# combo-03_1.net
KiCad netlist of a schematic drawn in EAGLE
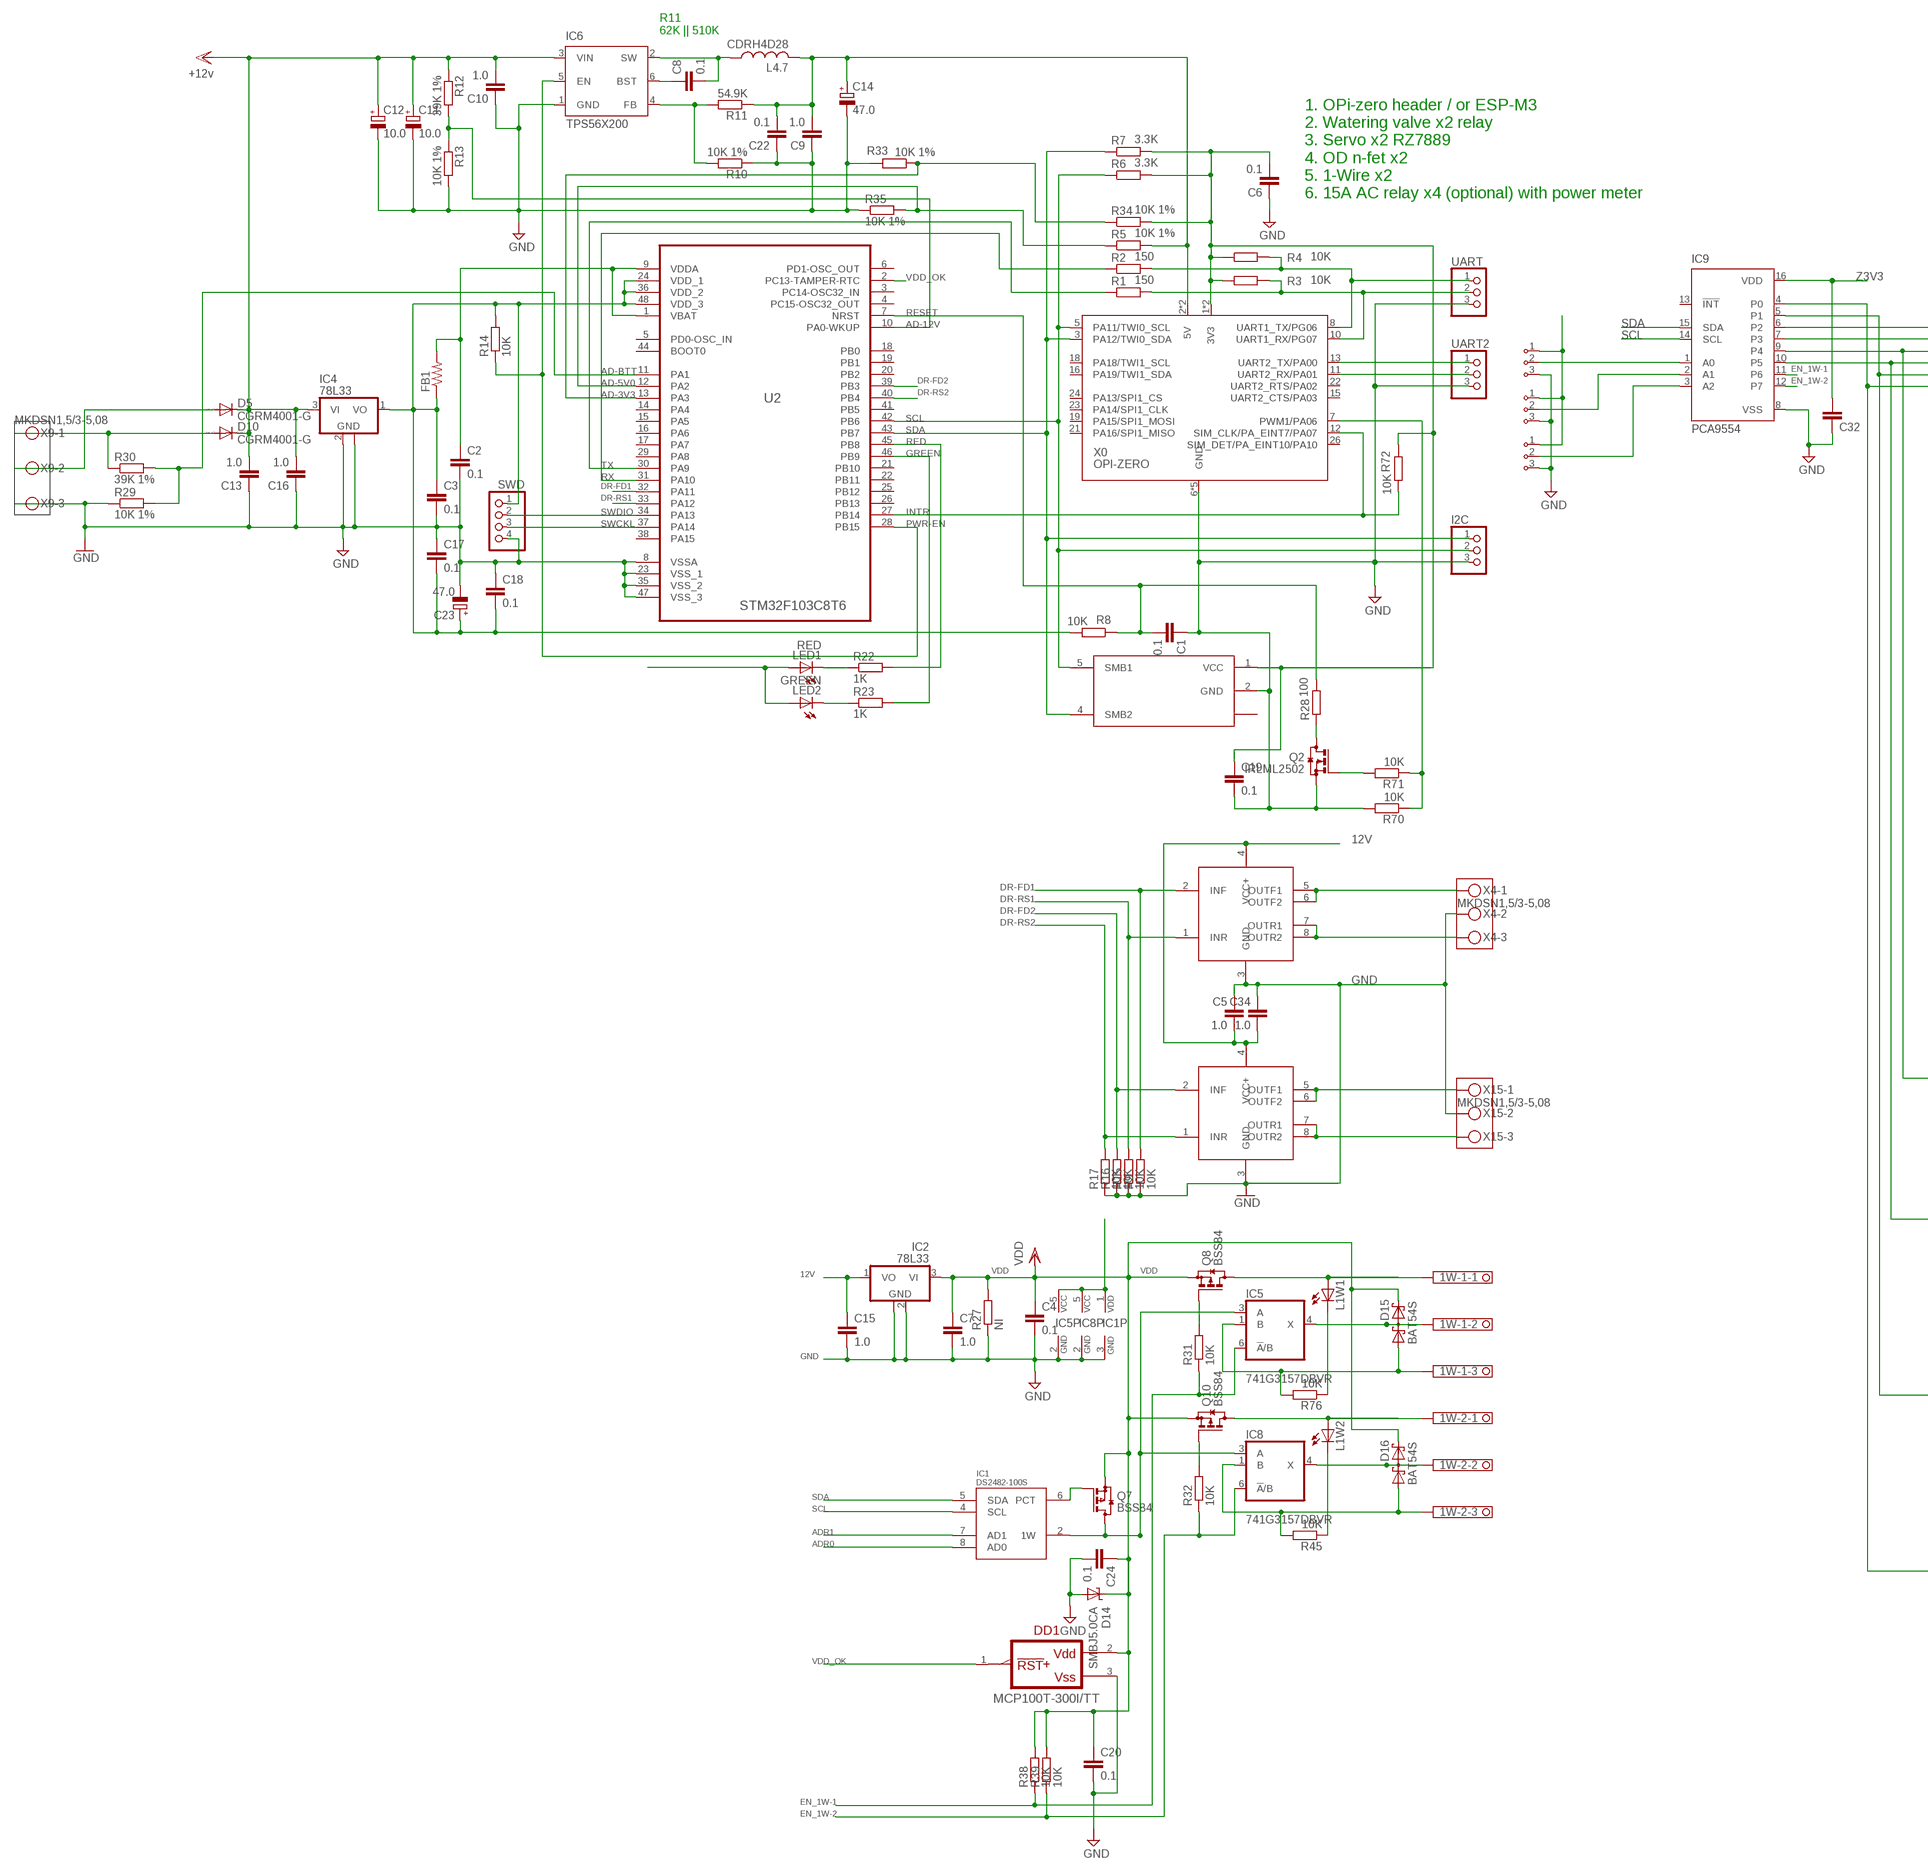
[diagram p0: schematic, sheet 1, part 1 of 2]
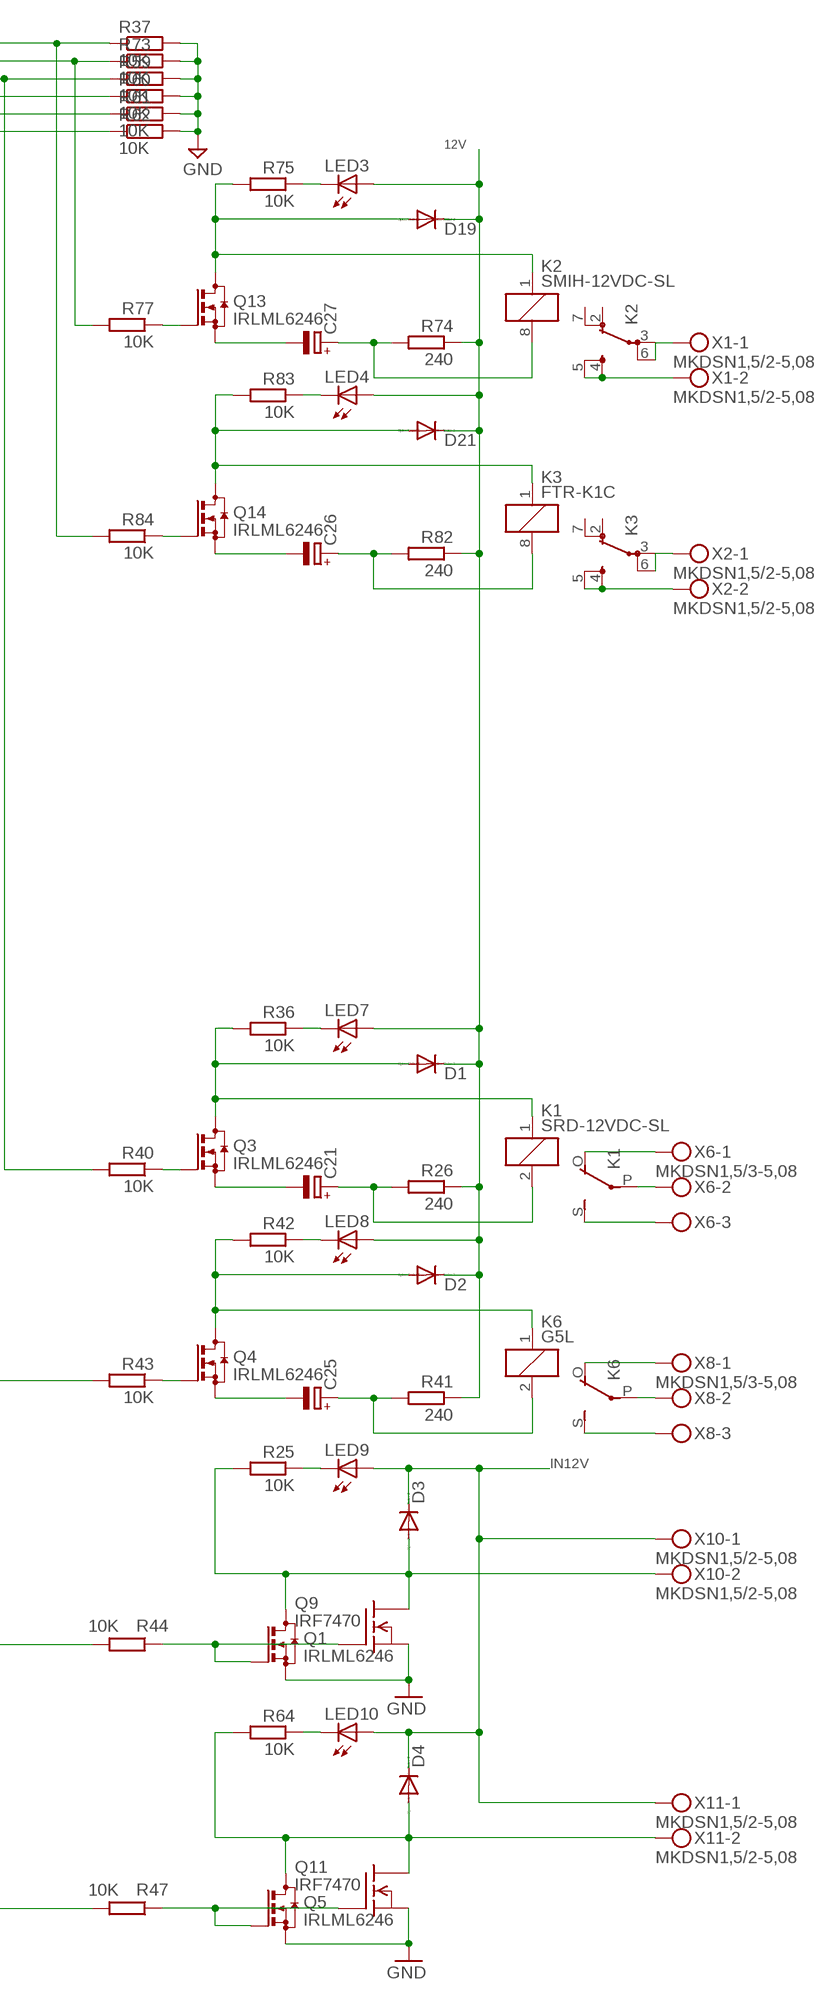
[diagram p1: schematic, sheet 1, part 2 of 2]

(export (version "E")
  (design (tool "Eeschema 10.0.6"))
  (components
    (comp (ref "1W-1")
      (value "1751251")
      (footprint "eagle-import:1751251")
      (libsource (lib "eagle-import") (part "1751251"))
    )
    (comp (ref "1W-2")
      (value "1751251")
      (footprint "eagle-import:1751251")
      (libsource (lib "eagle-import") (part "1751251"))
    )
    (comp (ref "A0")
      (value "ADDR3PIN0603")
      (footprint "eagle-import:0603-3PIN")
      (libsource (lib "eagle-import") (part "ADDR3PIN0603"))
    )
    (comp (ref "A1")
      (value "ADDR3PIN0603")
      (footprint "eagle-import:0603-3PIN")
      (libsource (lib "eagle-import") (part "ADDR3PIN0603"))
    )
    (comp (ref "A2")
      (value "ADDR3PIN0603")
      (footprint "eagle-import:0603-3PIN")
      (libsource (lib "eagle-import") (part "ADDR3PIN0603"))
    )
    (comp (ref "C1")
      (value "0.1")
      (footprint "eagle-import:C0603")
      (libsource (lib "eagle-import") (part "C-EUC0603"))
    )
    (comp (ref "C2")
      (value "0.1")
      (footprint "eagle-import:C0603")
      (libsource (lib "eagle-import") (part "C-EUC0603"))
    )
    (comp (ref "C3")
      (value "0.1")
      (footprint "eagle-import:C0603")
      (libsource (lib "eagle-import") (part "C-EUC0603"))
    )
    (comp (ref "C4")
      (value "0.1")
      (footprint "eagle-import:C0603")
      (libsource (lib "eagle-import") (part "C-EUC0603"))
    )
    (comp (ref "C5")
      (value "1.0")
      (footprint "eagle-import:C0805")
      (libsource (lib "eagle-import") (part "C-EUC0805"))
    )
    (comp (ref "C6")
      (value "0.1")
      (footprint "eagle-import:C0805")
      (libsource (lib "eagle-import") (part "C-EUC0805"))
    )
    (comp (ref "C7")
      (value "1.0")
      (footprint "eagle-import:C0805")
      (libsource (lib "eagle-import") (part "C-EUC0805"))
    )
    (comp (ref "C8")
      (value "0.1")
      (footprint "eagle-import:C0805")
      (libsource (lib "eagle-import") (part "C-EUC0805"))
    )
    (comp (ref "C9")
      (value "1.0")
      (footprint "eagle-import:C0805")
      (libsource (lib "eagle-import") (part "C-EUC0805"))
    )
    (comp (ref "C10")
      (value "1.0")
      (footprint "eagle-import:C1206")
      (libsource (lib "eagle-import") (part "C-EUC1206"))
    )
    (comp (ref "C11")
      (value "10.0")
      (footprint "eagle-import:C_6032-28R")
      (libsource (lib "eagle-import") (part "CPOL-EUC/6032-28R"))
    )
    (comp (ref "C12")
      (value "10.0")
      (footprint "eagle-import:C_6032-28R")
      (libsource (lib "eagle-import") (part "CPOL-EUC/6032-28R"))
    )
    (comp (ref "C13")
      (value "1.0")
      (footprint "eagle-import:C1206")
      (libsource (lib "eagle-import") (part "C-EUC1206"))
    )
    (comp (ref "C14")
      (value "47.0")
      (footprint "eagle-import:B_3528-21R")
      (libsource (lib "eagle-import") (part "CPOL-EUB/3528-21R"))
    )
    (comp (ref "C15")
      (value "1.0")
      (footprint "eagle-import:C0805")
      (libsource (lib "eagle-import") (part "C-EUC0805"))
    )
    (comp (ref "C16")
      (value "1.0")
      (footprint "eagle-import:C1206")
      (libsource (lib "eagle-import") (part "C-EUC1206"))
    )
    (comp (ref "C17")
      (value "0.1")
      (footprint "eagle-import:C0603")
      (libsource (lib "eagle-import") (part "C-EUC0603"))
    )
    (comp (ref "C18")
      (value "0.1")
      (footprint "eagle-import:C0603")
      (libsource (lib "eagle-import") (part "C-EUC0603"))
    )
    (comp (ref "C19")
      (value "0.1")
      (footprint "eagle-import:C0603")
      (libsource (lib "eagle-import") (part "C-EUC0603"))
    )
    (comp (ref "C20")
      (value "0.1")
      (footprint "eagle-import:C0603")
      (libsource (lib "eagle-import") (part "C-EUC0603"))
    )
    (comp (ref "C21")
      (value "CPOL-EUE3.5-8")
      (footprint "eagle-import:E3,5-8")
      (libsource (lib "eagle-import") (part "CPOL-EUE3.5-8"))
    )
    (comp (ref "C22")
      (value "0.1")
      (footprint "eagle-import:C0805")
      (libsource (lib "eagle-import") (part "C-EUC0805"))
    )
    (comp (ref "C23")
      (value "47.0")
      (footprint "eagle-import:B_3528-21R")
      (libsource (lib "eagle-import") (part "CPOL-EUB/3528-21R"))
    )
    (comp (ref "C24")
      (value "0.1")
      (footprint "eagle-import:C0603")
      (libsource (lib "eagle-import") (part "C-EUC0603"))
    )
    (comp (ref "C25")
      (value "CPOL-EUE3.5-8")
      (footprint "eagle-import:E3,5-8")
      (libsource (lib "eagle-import") (part "CPOL-EUE3.5-8"))
    )
    (comp (ref "C26")
      (value "CPOL-EUE3.5-8")
      (footprint "eagle-import:E3,5-8")
      (libsource (lib "eagle-import") (part "CPOL-EUE3.5-8"))
    )
    (comp (ref "C27")
      (value "CPOL-EUE3.5-8")
      (footprint "eagle-import:E3,5-8")
      (libsource (lib "eagle-import") (part "CPOL-EUE3.5-8"))
    )
    (comp (ref "C32")
      (value "C-EUC0805")
      (footprint "eagle-import:C0805")
      (libsource (lib "eagle-import") (part "C-EUC0805"))
    )
    (comp (ref "C34")
      (value "1.0")
      (footprint "eagle-import:C0805")
      (libsource (lib "eagle-import") (part "C-EUC0805"))
    )
    (comp (ref "D1")
      (value "DIODE-SOD123")
      (footprint "eagle-import:SOD123")
      (libsource (lib "eagle-import") (part "DIODE-SOD123"))
    )
    (comp (ref "D2")
      (value "DIODE-SOD123")
      (footprint "eagle-import:SOD123")
      (libsource (lib "eagle-import") (part "DIODE-SOD123"))
    )
    (comp (ref "D3")
      (value "DIODE-SOD123")
      (footprint "eagle-import:SOD123")
      (libsource (lib "eagle-import") (part "DIODE-SOD123"))
    )
    (comp (ref "D4")
      (value "DIODE-SOD123")
      (footprint "eagle-import:SOD123")
      (libsource (lib "eagle-import") (part "DIODE-SOD123"))
    )
    (comp (ref "D5")
      (value "CGRM4001-G")
      (footprint "eagle-import:SOD-123_MINI-SMA")
      (libsource (lib "eagle-import") (part "CGRM400-G1"))
    )
    (comp (ref "D10")
      (value "CGRM4001-G")
      (footprint "eagle-import:SOD-123_MINI-SMA")
      (libsource (lib "eagle-import") (part "CGRM400-G1"))
    )
    (comp (ref "D14")
      (value "SMBJ5.0CA")
      (footprint "eagle-import:SMBJ")
      (libsource (lib "eagle-import") (part "SUPPRESSOR-SMBJ"))
    )
    (comp (ref "D15")
      (value "BAT54S")
      (footprint "eagle-import:SOT23")
      (libsource (lib "eagle-import") (part "BAT54S"))
    )
    (comp (ref "D16")
      (value "BAT54S")
      (footprint "eagle-import:SOT23")
      (libsource (lib "eagle-import") (part "BAT54S"))
    )
    (comp (ref "D19")
      (value "DIODE-SOD123")
      (footprint "eagle-import:SOD123")
      (libsource (lib "eagle-import") (part "DIODE-SOD123"))
    )
    (comp (ref "D21")
      (value "DIODE-SOD123")
      (footprint "eagle-import:SOD123")
      (libsource (lib "eagle-import") (part "DIODE-SOD123"))
    )
    (comp (ref "DD1")
      (value "MCP100T-300I/TT")
      (footprint "eagle-import:SOT23")
      (libsource (lib "eagle-import") (part "MCP100T-300I/TT"))
    )
    (comp (ref "FB1")
      (value "R-US_R0805")
      (footprint "eagle-import:R0805")
      (libsource (lib "eagle-import") (part "R-US_R0805"))
    )
    (comp (ref "I2C")
      (value "PINHD-1X3")
      (footprint "eagle-import:1X03")
      (libsource (lib "eagle-import") (part "PINHD-1X3"))
    )
    (comp (ref "IC1")
      (value "DS2482-100S")
      (footprint "eagle-import:SO08")
      (libsource (lib "eagle-import") (part "DS2482-100S"))
    )
    (comp (ref "IC2")
      (value "78L33")
      (footprint "eagle-import:SOT89")
      (libsource (lib "eagle-import") (part "78LF05"))
    )
    (comp (ref "IC3")
      (value "RZ7889")
      (footprint "eagle-import:SO8")
      (libsource (lib "eagle-import") (part "RZ7889"))
    )
    (comp (ref "IC4")
      (value "78L33")
      (footprint "eagle-import:SOT89")
      (libsource (lib "eagle-import") (part "78LF05"))
    )
    (comp (ref "IC5")
      (value "741G3157DBVR")
      (footprint "eagle-import:DBV_R-PDSO-G6")
      (libsource (lib "eagle-import") (part "741G3157DBVR"))
    )
    (comp (ref "IC6")
      (value "TPS56X200")
      (footprint "eagle-import:TSOT23-6_DDC")
      (libsource (lib "eagle-import") (part "TPS56X200"))
    )
    (comp (ref "IC7")
      (value "LTC1694")
      (footprint "eagle-import:SOT23-5")
      (libsource (lib "eagle-import") (part "LTC1694"))
    )
    (comp (ref "IC8")
      (value "741G3157DBVR")
      (footprint "eagle-import:DBV_R-PDSO-G6")
      (libsource (lib "eagle-import") (part "741G3157DBVR"))
    )
    (comp (ref "IC9")
      (value "PCA9554")
      (footprint "eagle-import:SO16W")
      (fields (field (name "MPN") "PCF8574T/3,512"))
      (libsource (lib "eagle-import") (part "PCF8574T"))
    )
    (comp (ref "IC10")
      (value "RZ7889")
      (footprint "eagle-import:SO8")
      (libsource (lib "eagle-import") (part "RZ7889"))
    )
    (comp (ref "K1")
      (value "SRD-12VDC-SL")
      (footprint "eagle-import:G5LE")
      (libsource (lib "eagle-import") (part "G5L"))
    )
    (comp (ref "K2")
      (value "SMIH-12VDC-SL")
      (footprint "eagle-import:FTR-K1C")
      (libsource (lib "eagle-import") (part "FTR-K1C"))
    )
    (comp (ref "K3")
      (value "FTR-K1C")
      (footprint "eagle-import:FTR-K1C")
      (libsource (lib "eagle-import") (part "FTR-K1C"))
    )
    (comp (ref "K6")
      (value "G5L")
      (footprint "eagle-import:G5LE")
      (libsource (lib "eagle-import") (part "G5L"))
    )
    (comp (ref "L1W1")
      (value "LEDSMT1206")
      (footprint "eagle-import:1206")
      (libsource (lib "eagle-import") (part "LEDSMT1206"))
    )
    (comp (ref "L1W2")
      (value "LEDSMT1206")
      (footprint "eagle-import:1206")
      (libsource (lib "eagle-import") (part "LEDSMT1206"))
    )
    (comp (ref "L4.7")
      (value "CDRH4D28")
      (footprint "eagle-import:CDRH4D28")
      (libsource (lib "eagle-import") (part "CDRH4D28"))
    )
    (comp (ref "LED1")
      (value "RED")
      (footprint "eagle-import:CHIPLED_1206")
      (libsource (lib "eagle-import") (part "LEDCHIPLED_1206"))
    )
    (comp (ref "LED2")
      (value "GREEN")
      (footprint "eagle-import:CHIPLED_1206")
      (libsource (lib "eagle-import") (part "LEDCHIPLED_1206"))
    )
    (comp (ref "LED3")
      (value "LEDSMT1206")
      (footprint "eagle-import:1206")
      (libsource (lib "eagle-import") (part "LEDSMT1206"))
    )
    (comp (ref "LED4")
      (value "LEDSMT1206")
      (footprint "eagle-import:1206")
      (libsource (lib "eagle-import") (part "LEDSMT1206"))
    )
    (comp (ref "LED7")
      (value "LEDSMT1206")
      (footprint "eagle-import:1206")
      (libsource (lib "eagle-import") (part "LEDSMT1206"))
    )
    (comp (ref "LED8")
      (value "LEDSMT1206")
      (footprint "eagle-import:1206")
      (libsource (lib "eagle-import") (part "LEDSMT1206"))
    )
    (comp (ref "LED9")
      (value "LEDSMT1206")
      (footprint "eagle-import:1206")
      (libsource (lib "eagle-import") (part "LEDSMT1206"))
    )
    (comp (ref "LED10")
      (value "LEDSMT1206")
      (footprint "eagle-import:1206")
      (libsource (lib "eagle-import") (part "LEDSMT1206"))
    )
    (comp (ref "Q1")
      (value "IRLML6246")
      (footprint "eagle-import:SOT23")
      (libsource (lib "eagle-import") (part "BSS123"))
    )
    (comp (ref "Q2")
      (value "IRLML2502")
      (footprint "eagle-import:SOT23")
      (libsource (lib "eagle-import") (part "IRLML2502"))
    )
    (comp (ref "Q3")
      (value "IRLML6246")
      (footprint "eagle-import:SOT23")
      (libsource (lib "eagle-import") (part "BSS123"))
    )
    (comp (ref "Q4")
      (value "IRLML6246")
      (footprint "eagle-import:SOT23")
      (libsource (lib "eagle-import") (part "BSS123"))
    )
    (comp (ref "Q5")
      (value "IRLML6246")
      (footprint "eagle-import:SOT23")
      (libsource (lib "eagle-import") (part "BSS123"))
    )
    (comp (ref "Q7")
      (value "BSS84")
      (footprint "eagle-import:SOT23")
      (libsource (lib "eagle-import") (part "BSS84"))
    )
    (comp (ref "Q8")
      (value "BSS84")
      (footprint "eagle-import:SOT23")
      (libsource (lib "eagle-import") (part "BSS84"))
    )
    (comp (ref "Q9")
      (value "IRF7470")
      (footprint "eagle-import:SO-8")
      (libsource (lib "eagle-import") (part "FDS5680"))
    )
    (comp (ref "Q10")
      (value "BSS84")
      (footprint "eagle-import:SOT23")
      (libsource (lib "eagle-import") (part "BSS84"))
    )
    (comp (ref "Q11")
      (value "IRF7470")
      (footprint "eagle-import:SO-8")
      (libsource (lib "eagle-import") (part "FDS5680"))
    )
    (comp (ref "Q13")
      (value "IRLML6246")
      (footprint "eagle-import:SOT23")
      (libsource (lib "eagle-import") (part "BSS123"))
    )
    (comp (ref "Q14")
      (value "IRLML6246")
      (footprint "eagle-import:SOT23")
      (libsource (lib "eagle-import") (part "BSS123"))
    )
    (comp (ref "R1")
      (value "150")
      (footprint "eagle-import:R0603")
      (libsource (lib "eagle-import") (part "R-EU_R0603"))
    )
    (comp (ref "R2")
      (value "150")
      (footprint "eagle-import:R0603")
      (libsource (lib "eagle-import") (part "R-EU_R0603"))
    )
    (comp (ref "R3")
      (value "10K")
      (footprint "eagle-import:R0603")
      (libsource (lib "eagle-import") (part "R-EU_R0603"))
    )
    (comp (ref "R4")
      (value "10K")
      (footprint "eagle-import:R0603")
      (libsource (lib "eagle-import") (part "R-EU_R0603"))
    )
    (comp (ref "R5")
      (value "10K 1%")
      (footprint "eagle-import:R0603")
      (libsource (lib "eagle-import") (part "R-EU_R0603"))
    )
    (comp (ref "R6")
      (value "3.3K")
      (footprint "eagle-import:R0603")
      (libsource (lib "eagle-import") (part "R-EU_R0603"))
    )
    (comp (ref "R7")
      (value "3.3K")
      (footprint "eagle-import:R0603")
      (libsource (lib "eagle-import") (part "R-EU_R0603"))
    )
    (comp (ref "R8")
      (value "10K")
      (footprint "eagle-import:R0603")
      (libsource (lib "eagle-import") (part "R-EU_R0603"))
    )
    (comp (ref "R9")
      (value "10K")
      (footprint "eagle-import:R0603")
      (libsource (lib "eagle-import") (part "R-EU_R0603"))
    )
    (comp (ref "R10")
      (value "10K 1%")
      (footprint "eagle-import:R0603")
      (libsource (lib "eagle-import") (part "R-EU_R0603"))
    )
    (comp (ref "R11")
      (value "54.9K")
      (footprint "eagle-import:R0603")
      (libsource (lib "eagle-import") (part "R-EU_R0603"))
    )
    (comp (ref "R12")
      (value "39K 1%")
      (footprint "eagle-import:R0603")
      (libsource (lib "eagle-import") (part "R-EU_R0603"))
    )
    (comp (ref "R13")
      (value "10K 1%")
      (footprint "eagle-import:R0603")
      (libsource (lib "eagle-import") (part "R-EU_R0603"))
    )
    (comp (ref "R14")
      (value "10K")
      (footprint "eagle-import:R0603")
      (libsource (lib "eagle-import") (part "R-EU_R0603"))
    )
    (comp (ref "R15")
      (value "10K")
      (footprint "eagle-import:R0603")
      (libsource (lib "eagle-import") (part "R-EU_R0603"))
    )
    (comp (ref "R16")
      (value "10K")
      (footprint "eagle-import:R0603")
      (libsource (lib "eagle-import") (part "R-EU_R0603"))
    )
    (comp (ref "R17")
      (value "10K")
      (footprint "eagle-import:R0603")
      (libsource (lib "eagle-import") (part "R-EU_R0603"))
    )
    (comp (ref "R22")
      (value "1K")
      (footprint "eagle-import:R0603")
      (libsource (lib "eagle-import") (part "R-EU_R0603"))
    )
    (comp (ref "R23")
      (value "1K")
      (footprint "eagle-import:R0603")
      (libsource (lib "eagle-import") (part "R-EU_R0603"))
    )
    (comp (ref "R25")
      (value "10K")
      (footprint "eagle-import:R0603")
      (libsource (lib "eagle-import") (part "R-EU_R0603"))
    )
    (comp (ref "R26")
      (value "240")
      (footprint "eagle-import:R1206")
      (libsource (lib "eagle-import") (part "R-EU_R1206"))
    )
    (comp (ref "R27")
      (value "NI")
      (footprint "eagle-import:R0603")
      (libsource (lib "eagle-import") (part "R-EU_R0603"))
    )
    (comp (ref "R28")
      (value "100")
      (footprint "eagle-import:R0603")
      (libsource (lib "eagle-import") (part "R-EU_R0603"))
    )
    (comp (ref "R29")
      (value "10K 1%")
      (footprint "eagle-import:R0603")
      (libsource (lib "eagle-import") (part "R-EU_R0603"))
    )
    (comp (ref "R30")
      (value "39K 1%")
      (footprint "eagle-import:R0603")
      (libsource (lib "eagle-import") (part "R-EU_R0603"))
    )
    (comp (ref "R31")
      (value "10K")
      (footprint "eagle-import:R0603")
      (libsource (lib "eagle-import") (part "R-EU_R0603"))
    )
    (comp (ref "R32")
      (value "10K")
      (footprint "eagle-import:R0603")
      (libsource (lib "eagle-import") (part "R-EU_R0603"))
    )
    (comp (ref "R33")
      (value "10K 1%")
      (footprint "eagle-import:R0603")
      (libsource (lib "eagle-import") (part "R-EU_R0603"))
    )
    (comp (ref "R34")
      (value "10K 1%")
      (footprint "eagle-import:R0603")
      (libsource (lib "eagle-import") (part "R-EU_R0603"))
    )
    (comp (ref "R35")
      (value "10K 1%")
      (footprint "eagle-import:R0603")
      (libsource (lib "eagle-import") (part "R-EU_R0603"))
    )
    (comp (ref "R36")
      (value "10K")
      (footprint "eagle-import:R0603")
      (libsource (lib "eagle-import") (part "R-EU_R0603"))
    )
    (comp (ref "R37")
      (value "10K")
      (footprint "eagle-import:R0603")
      (libsource (lib "eagle-import") (part "R-EU_R0603"))
    )
    (comp (ref "R38")
      (value "10K")
      (footprint "eagle-import:R0603")
      (libsource (lib "eagle-import") (part "R-EU_R0603"))
    )
    (comp (ref "R39")
      (value "10K")
      (footprint "eagle-import:R0603")
      (libsource (lib "eagle-import") (part "R-EU_R0603"))
    )
    (comp (ref "R40")
      (value "10K")
      (footprint "eagle-import:R0603")
      (libsource (lib "eagle-import") (part "R-EU_R0603"))
    )
    (comp (ref "R41")
      (value "240")
      (footprint "eagle-import:R1206")
      (libsource (lib "eagle-import") (part "R-EU_R1206"))
    )
    (comp (ref "R42")
      (value "10K")
      (footprint "eagle-import:R0603")
      (libsource (lib "eagle-import") (part "R-EU_R0603"))
    )
    (comp (ref "R43")
      (value "10K")
      (footprint "eagle-import:R0603")
      (libsource (lib "eagle-import") (part "R-EU_R0603"))
    )
    (comp (ref "R44")
      (value "10K")
      (footprint "eagle-import:R0603")
      (libsource (lib "eagle-import") (part "R-EU_R0603"))
    )
    (comp (ref "R45")
      (value "10K")
      (footprint "eagle-import:R0603")
      (libsource (lib "eagle-import") (part "R-EU_R0603"))
    )
    (comp (ref "R47")
      (value "10K")
      (footprint "eagle-import:R0603")
      (libsource (lib "eagle-import") (part "R-EU_R0603"))
    )
    (comp (ref "R59")
      (value "10K")
      (footprint "eagle-import:R0603")
      (libsource (lib "eagle-import") (part "R-EU_R0603"))
    )
    (comp (ref "R60")
      (value "10K")
      (footprint "eagle-import:R0603")
      (libsource (lib "eagle-import") (part "R-EU_R0603"))
    )
    (comp (ref "R61")
      (value "10K")
      (footprint "eagle-import:R0603")
      (libsource (lib "eagle-import") (part "R-EU_R0603"))
    )
    (comp (ref "R62")
      (value "10K")
      (footprint "eagle-import:R0603")
      (libsource (lib "eagle-import") (part "R-EU_R0603"))
    )
    (comp (ref "R64")
      (value "10K")
      (footprint "eagle-import:R0603")
      (libsource (lib "eagle-import") (part "R-EU_R0603"))
    )
    (comp (ref "R70")
      (value "10K")
      (footprint "eagle-import:R0603")
      (libsource (lib "eagle-import") (part "R-EU_R0603"))
    )
    (comp (ref "R71")
      (value "10K")
      (footprint "eagle-import:R0603")
      (libsource (lib "eagle-import") (part "R-EU_R0603"))
    )
    (comp (ref "R72")
      (value "10K")
      (footprint "eagle-import:R0603")
      (libsource (lib "eagle-import") (part "R-EU_R0603"))
    )
    (comp (ref "R73")
      (value "10K")
      (footprint "eagle-import:R0603")
      (libsource (lib "eagle-import") (part "R-EU_R0603"))
    )
    (comp (ref "R74")
      (value "240")
      (footprint "eagle-import:R1206")
      (libsource (lib "eagle-import") (part "R-EU_R1206"))
    )
    (comp (ref "R75")
      (value "10K")
      (footprint "eagle-import:R0603")
      (libsource (lib "eagle-import") (part "R-EU_R0603"))
    )
    (comp (ref "R76")
      (value "10K")
      (footprint "eagle-import:R0603")
      (libsource (lib "eagle-import") (part "R-EU_R0603"))
    )
    (comp (ref "R77")
      (value "10K")
      (footprint "eagle-import:R0603")
      (libsource (lib "eagle-import") (part "R-EU_R0603"))
    )
    (comp (ref "R82")
      (value "240")
      (footprint "eagle-import:R1206")
      (libsource (lib "eagle-import") (part "R-EU_R1206"))
    )
    (comp (ref "R83")
      (value "10K")
      (footprint "eagle-import:R0603")
      (libsource (lib "eagle-import") (part "R-EU_R0603"))
    )
    (comp (ref "R84")
      (value "10K")
      (footprint "eagle-import:R0603")
      (libsource (lib "eagle-import") (part "R-EU_R0603"))
    )
    (comp (ref "SWD")
      (value "PINHD-1X4")
      (footprint "eagle-import:1X04")
      (libsource (lib "eagle-import") (part "PINHD-1X4"))
    )
    (comp (ref "U2")
      (value "STM32F103C8T6")
      (footprint "eagle-import:QFP50P900X900X160-48N")
      (fields (field (name "MPN") "STM32F100CBT6B"))
      (libsource (lib "eagle-import") (part "STM32F100CBT6B"))
    )
    (comp (ref "UART")
      (value "PINHD-1X3")
      (footprint "eagle-import:1X03")
      (libsource (lib "eagle-import") (part "PINHD-1X3"))
    )
    (comp (ref "UART2")
      (value "PINHD-1X3")
      (footprint "eagle-import:1X03")
      (libsource (lib "eagle-import") (part "PINHD-1X3"))
    )
    (comp (ref "X0")
      (value "OPI-ZERO")
      (footprint "eagle-import:OPI0")
      (libsource (lib "eagle-import") (part "OPI-ZERO"))
    )
    (comp (ref "X1")
      (value "MKDSN1,5/2-5,08")
      (footprint "eagle-import:MKDSN1,5_2-5,08")
      (libsource (lib "eagle-import") (part "MKDSN1,5/2-5,08"))
    )
    (comp (ref "X2")
      (value "MKDSN1,5/2-5,08")
      (footprint "eagle-import:MKDSN1,5_2-5,08")
      (libsource (lib "eagle-import") (part "MKDSN1,5/2-5,08"))
    )
    (comp (ref "X4")
      (value "MKDSN1,5/3-5,08")
      (footprint "eagle-import:MKDSN1,5_3-5,08")
      (libsource (lib "eagle-import") (part "MKDSN1,5/3-5,08"))
    )
    (comp (ref "X6")
      (value "MKDSN1,5/3-5,08")
      (footprint "eagle-import:MKDSN1,5_3-5,08")
      (libsource (lib "eagle-import") (part "MKDSN1,5/3-5,08"))
    )
    (comp (ref "X8")
      (value "MKDSN1,5/3-5,08")
      (footprint "eagle-import:MKDSN1,5_3-5,08")
      (libsource (lib "eagle-import") (part "MKDSN1,5/3-5,08"))
    )
    (comp (ref "X9")
      (value "MKDSN1,5/3-5,08")
      (footprint "eagle-import:MKDSN1,5_3-5,08")
      (libsource (lib "eagle-import") (part "MKDSN1,5/3-5,08"))
    )
    (comp (ref "X10")
      (value "MKDSN1,5/2-5,08")
      (footprint "eagle-import:MKDSN1,5_2-5,08")
      (libsource (lib "eagle-import") (part "MKDSN1,5/2-5,08"))
    )
    (comp (ref "X11")
      (value "MKDSN1,5/2-5,08")
      (footprint "eagle-import:MKDSN1,5_2-5,08")
      (libsource (lib "eagle-import") (part "MKDSN1,5/2-5,08"))
    )
    (comp (ref "X15")
      (value "MKDSN1,5/3-5,08")
      (footprint "eagle-import:MKDSN1,5_3-5,08")
      (libsource (lib "eagle-import") (part "MKDSN1,5/3-5,08"))
    )
  )
  (nets
    (net (code "1") (name "+12v") (class "Default")
      (node (ref "C10") (pin "2") (pinfunction "2_2") (pintype "passive"))
      (node (ref "C11") (pin "+") (pinfunction "+_+") (pintype "passive"))
      (node (ref "C12") (pin "+") (pinfunction "+_+") (pintype "passive"))
      (node (ref "C13") (pin "2") (pinfunction "2_2") (pintype "passive"))
      (node (ref "C15") (pin "1") (pinfunction "1_1") (pintype "passive"))
      (node (ref "C16") (pin "2") (pinfunction "2_2") (pintype "passive"))
      (node (ref "C34") (pin "2") (pinfunction "2_2") (pintype "passive"))
      (node (ref "C5") (pin "2") (pinfunction "2_2") (pintype "passive"))
      (node (ref "D1") (pin "C") (pinfunction "C_C") (pintype "passive"))
      (node (ref "D10") (pin "C") (pinfunction "C_C") (pintype "passive"))
      (node (ref "D19") (pin "C") (pinfunction "C_C") (pintype "passive"))
      (node (ref "D2") (pin "C") (pinfunction "C_C") (pintype "passive"))
      (node (ref "D21") (pin "C") (pinfunction "C_C") (pintype "passive"))
      (node (ref "D5") (pin "C") (pinfunction "C_C") (pintype "passive"))
      (node (ref "IC10") (pin "4") (pinfunction "VCC+_4") (pintype "bidirectional"))
      (node (ref "IC2") (pin "1") (pinfunction "VO_1") (pintype "passive"))
      (node (ref "IC3") (pin "4") (pinfunction "VCC+_4") (pintype "bidirectional"))
      (node (ref "IC4") (pin "3") (pinfunction "VI_3") (pintype "input"))
      (node (ref "IC6") (pin "3") (pinfunction "VIN_3") (pintype "input"))
      (node (ref "LED3") (pin "A") (pinfunction "A_A") (pintype "passive"))
      (node (ref "LED4") (pin "A") (pinfunction "A_A") (pintype "passive"))
      (node (ref "LED7") (pin "A") (pinfunction "A_A") (pintype "passive"))
      (node (ref "LED8") (pin "A") (pinfunction "A_A") (pintype "passive"))
      (node (ref "R12") (pin "1") (pinfunction "1_1") (pintype "passive"))
      (node (ref "R26") (pin "1") (pinfunction "1_1") (pintype "passive"))
      (node (ref "R41") (pin "1") (pinfunction "1_1") (pintype "passive"))
      (node (ref "R74") (pin "1") (pinfunction "1_1") (pintype "passive"))
      (node (ref "R82") (pin "1") (pinfunction "1_1") (pintype "passive"))
    )
    (net (code "2") (name "/AD-3V3") (class "Default")
      (node (ref "R33") (pin "1") (pinfunction "1_1") (pintype "passive"))
      (node (ref "R34") (pin "1") (pinfunction "1_1") (pintype "passive"))
      (node (ref "U2") (pin "13") (pinfunction "PA3_13") (pintype "bidirectional"))
    )
    (net (code "3") (name "/AD-5V0") (class "Default")
      (node (ref "R35") (pin "2") (pinfunction "2_2") (pintype "passive"))
      (node (ref "R5") (pin "1") (pinfunction "1_1") (pintype "passive"))
      (node (ref "U2") (pin "12") (pinfunction "PA2_12") (pintype "bidirectional"))
    )
    (net (code "4") (name "/AD-12V") (class "Default")
      (node (ref "R12") (pin "2") (pinfunction "2_2") (pintype "passive"))
      (node (ref "R13") (pin "1") (pinfunction "1_1") (pintype "passive"))
      (node (ref "U2") (pin "10") (pinfunction "PA0-WKUP_10") (pintype "bidirectional"))
    )
    (net (code "5") (name "/AD-BTT") (class "Default")
      (node (ref "R29") (pin "2") (pinfunction "2_2") (pintype "passive"))
      (node (ref "R30") (pin "2") (pinfunction "2_2") (pintype "passive"))
      (node (ref "U2") (pin "11") (pinfunction "PA1_11") (pintype "bidirectional"))
    )
    (net (code "6") (name "/ADR0") (class "Default")
      (node (ref "A2") (pin "2") (pinfunction "P$1_2") (pintype "bidirectional"))
      (node (ref "IC1") (pin "8") (pinfunction "AD0_8") (pintype "input"))
      (node (ref "IC9") (pin "1") (pinfunction "A0_1") (pintype "input"))
    )
    (net (code "7") (name "/ADR1") (class "Default")
      (node (ref "A1") (pin "2") (pinfunction "P$1_2") (pintype "bidirectional"))
      (node (ref "IC1") (pin "7") (pinfunction "AD1_7") (pintype "input"))
      (node (ref "IC9") (pin "2") (pinfunction "A1_2") (pintype "input"))
    )
    (net (code "8") (name "/DR-FD1") (class "Default")
      (node (ref "IC3") (pin "2") (pinfunction "INF_2") (pintype "bidirectional"))
      (node (ref "R9") (pin "2") (pinfunction "2_2") (pintype "passive"))
      (node (ref "U2") (pin "32") (pinfunction "PA11_32") (pintype "bidirectional"))
    )
    (net (code "9") (name "/DR-FD2") (class "Default")
      (node (ref "IC10") (pin "2") (pinfunction "INF_2") (pintype "bidirectional"))
      (node (ref "R16") (pin "2") (pinfunction "2_2") (pintype "passive"))
      (node (ref "U2") (pin "39") (pinfunction "PB3_39") (pintype "bidirectional"))
    )
    (net (code "10") (name "/DR-RS1") (class "Default")
      (node (ref "IC3") (pin "1") (pinfunction "INR_1") (pintype "bidirectional"))
      (node (ref "R15") (pin "2") (pinfunction "2_2") (pintype "passive"))
      (node (ref "U2") (pin "33") (pinfunction "PA12_33") (pintype "bidirectional"))
    )
    (net (code "11") (name "/DR-RS2") (class "Default")
      (node (ref "IC10") (pin "1") (pinfunction "INR_1") (pintype "bidirectional"))
      (node (ref "R17") (pin "2") (pinfunction "2_2") (pintype "passive"))
      (node (ref "U2") (pin "40") (pinfunction "PB4_40") (pintype "bidirectional"))
    )
    (net (code "12") (name "/EN_1W-1") (class "Default")
      (node (ref "IC5") (pin "6") (pinfunction "~{A}/B_6") (pintype "input"))
      (node (ref "IC9") (pin "11") (pinfunction "P6_11") (pintype "bidirectional"))
      (node (ref "R31") (pin "1") (pinfunction "1_1") (pintype "passive"))
      (node (ref "R38") (pin "1") (pinfunction "1_1") (pintype "passive"))
    )
    (net (code "13") (name "/EN_1W-2") (class "Default")
      (node (ref "IC8") (pin "6") (pinfunction "~{A}/B_6") (pintype "input"))
      (node (ref "IC9") (pin "12") (pinfunction "P7_12") (pintype "bidirectional"))
      (node (ref "R32") (pin "1") (pinfunction "1_1") (pintype "passive"))
      (node (ref "R39") (pin "1") (pinfunction "1_1") (pintype "passive"))
    )
    (net (code "14") (name "/GREEN") (class "Default")
      (node (ref "R23") (pin "2") (pinfunction "2_2") (pintype "passive"))
      (node (ref "U2") (pin "46") (pinfunction "PB9_46") (pintype "bidirectional"))
    )
    (net (code "15") (name "/IN12V") (class "Default")
      (node (ref "D3") (pin "C") (pinfunction "C_C") (pintype "passive"))
      (node (ref "D4") (pin "C") (pinfunction "C_C") (pintype "passive"))
      (node (ref "D5") (pin "A") (pinfunction "A_A") (pintype "passive"))
      (node (ref "LED10") (pin "A") (pinfunction "A_A") (pintype "passive"))
      (node (ref "LED9") (pin "A") (pinfunction "A_A") (pintype "passive"))
      (node (ref "X10") (pin "1") (pinfunction "KL_1") (pintype "passive"))
      (node (ref "X11") (pin "1") (pinfunction "KL_1") (pintype "passive"))
      (node (ref "X9") (pin "2") (pinfunction "KL_2") (pintype "passive"))
    )
    (net (code "16") (name "/INTR") (class "Default")
      (node (ref "R72") (pin "2") (pinfunction "2_2") (pintype "passive"))
      (node (ref "U2") (pin "27") (pinfunction "PB14_27") (pintype "bidirectional"))
      (node (ref "X0") (pin "12") (pinfunction "SIM_CLK/PA_EINT7/PA07_12") (pintype "bidirectional"))
    )
    (net (code "17") (name "/PWR-EN") (class "Default")
      (node (ref "IC6") (pin "5") (pinfunction "EN_5") (pintype "input"))
      (node (ref "R14") (pin "1") (pinfunction "1_1") (pintype "passive"))
      (node (ref "U2") (pin "28") (pinfunction "PB15_28") (pintype "bidirectional"))
    )
    (net (code "18") (name "/RED") (class "Default")
      (node (ref "R22") (pin "2") (pinfunction "2_2") (pintype "passive"))
      (node (ref "U2") (pin "45") (pinfunction "PB8_45") (pintype "bidirectional"))
    )
    (net (code "19") (name "/RESET") (class "Default")
      (node (ref "C1") (pin "2") (pinfunction "2_2") (pintype "passive"))
      (node (ref "R28") (pin "2") (pinfunction "2_2") (pintype "passive"))
      (node (ref "R8") (pin "1") (pinfunction "1_1") (pintype "passive"))
      (node (ref "U2") (pin "7") (pinfunction "NRST_7") (pintype "bidirectional"))
    )
    (net (code "20") (name "/RX") (class "Default")
      (node (ref "R2") (pin "1") (pinfunction "1_1") (pintype "passive"))
      (node (ref "U2") (pin "31") (pinfunction "PA10_31") (pintype "bidirectional"))
    )
    (net (code "21") (name "/SCL") (class "Default")
      (node (ref "I2C") (pin "2") (pinfunction "2_2") (pintype "passive"))
      (node (ref "IC1") (pin "4") (pinfunction "SCL_4") (pintype "input"))
      (node (ref "IC7") (pin "5") (pinfunction "SMB1_5") (pintype "bidirectional"))
      (node (ref "IC9") (pin "14") (pinfunction "SCL_14") (pintype "input"))
      (node (ref "R6") (pin "1") (pinfunction "1_1") (pintype "passive"))
      (node (ref "U2") (pin "42") (pinfunction "PB6_42") (pintype "bidirectional"))
      (node (ref "X0") (pin "5") (pinfunction "PA11/TWI0_SCL_5") (pintype "bidirectional"))
    )
    (net (code "22") (name "/SDA") (class "Default")
      (node (ref "I2C") (pin "1") (pinfunction "1_1") (pintype "passive"))
      (node (ref "IC1") (pin "5") (pinfunction "SDA_5") (pintype "bidirectional"))
      (node (ref "IC7") (pin "4") (pinfunction "SMB2_4") (pintype "bidirectional"))
      (node (ref "IC9") (pin "15") (pinfunction "SDA_15") (pintype "bidirectional"))
      (node (ref "R7") (pin "1") (pinfunction "1_1") (pintype "passive"))
      (node (ref "U2") (pin "43") (pinfunction "PB7_43") (pintype "bidirectional"))
      (node (ref "X0") (pin "3") (pinfunction "PA12/TWI0_SDA_3") (pintype "bidirectional"))
    )
    (net (code "23") (name "/SWCKL") (class "Default")
      (node (ref "SWD") (pin "3") (pinfunction "3_3") (pintype "passive"))
      (node (ref "U2") (pin "37") (pinfunction "PA14_37") (pintype "bidirectional"))
    )
    (net (code "24") (name "/SWDIO") (class "Default")
      (node (ref "SWD") (pin "2") (pinfunction "2_2") (pintype "passive"))
      (node (ref "U2") (pin "34") (pinfunction "PA13_34") (pintype "bidirectional"))
    )
    (net (code "25") (name "/TX") (class "Default")
      (node (ref "R1") (pin "1") (pinfunction "1_1") (pintype "passive"))
      (node (ref "U2") (pin "30") (pinfunction "PA9_30") (pintype "bidirectional"))
    )
    (net (code "26") (name "/VDD_OK") (class "Default")
      (node (ref "DD1") (pin "1") (pinfunction "~{RST}_1") (pintype "passive"))
      (node (ref "U2") (pin "2") (pinfunction "PC13-TAMPER-RTC_2") (pintype "bidirectional"))
    )
    (net (code "27") (name "/Z3V3") (class "Default")
      (node (ref "A0") (pin "1") (pinfunction "P$2_1") (pintype "power_in"))
      (node (ref "A1") (pin "1") (pinfunction "P$2_1") (pintype "power_in"))
      (node (ref "A2") (pin "1") (pinfunction "P$2_1") (pintype "power_in"))
      (node (ref "C19") (pin "1") (pinfunction "1_1") (pintype "passive"))
      (node (ref "C32") (pin "2") (pinfunction "2_2") (pintype "passive"))
      (node (ref "C6") (pin "2") (pinfunction "2_2") (pintype "passive"))
      (node (ref "IC1") (pin "1") (pinfunction "VDD_1") (pintype "power_in"))
      (node (ref "IC5") (pin "5") (pinfunction "VCC_5") (pintype "power_in"))
      (node (ref "IC7") (pin "1") (pinfunction "VCC_1") (pintype "power_in"))
      (node (ref "IC8") (pin "5") (pinfunction "VCC_5") (pintype "power_in"))
      (node (ref "IC9") (pin "16") (pinfunction "VDD_16") (pintype "power_in"))
      (node (ref "R3") (pin "1") (pinfunction "1_1") (pintype "passive"))
      (node (ref "R34") (pin "2") (pinfunction "2_2") (pintype "passive"))
      (node (ref "R4") (pin "1") (pinfunction "1_1") (pintype "passive"))
      (node (ref "R6") (pin "2") (pinfunction "2_2") (pintype "passive"))
      (node (ref "R7") (pin "2") (pinfunction "2_2") (pintype "passive"))
      (node (ref "R72") (pin "1") (pinfunction "1_1") (pintype "passive"))
      (node (ref "X0") (pin "1") (pinfunction "3V3_1") (pintype "power_in"))
      (node (ref "X0") (pin "17") (pinfunction "3V3_17") (pintype "power_in"))
    )
    (net (code "28") (name "GND") (class "Default")
      (node (ref "1W-1") (pin "3") (pinfunction "K_3") (pintype "passive"))
      (node (ref "1W-2") (pin "3") (pinfunction "K_3") (pintype "passive"))
      (node (ref "A0") (pin "3") (pinfunction "P$3_3") (pintype "power_in"))
      (node (ref "A1") (pin "3") (pinfunction "P$3_3") (pintype "power_in"))
      (node (ref "A2") (pin "3") (pinfunction "P$3_3") (pintype "power_in"))
      (node (ref "C1") (pin "1") (pinfunction "1_1") (pintype "passive"))
      (node (ref "C10") (pin "1") (pinfunction "1_1") (pintype "passive"))
      (node (ref "C11") (pin "-") (pinfunction "-_-") (pintype "passive"))
      (node (ref "C12") (pin "-") (pinfunction "-_-") (pintype "passive"))
      (node (ref "C13") (pin "1") (pinfunction "1_1") (pintype "passive"))
      (node (ref "C14") (pin "-") (pinfunction "-_-") (pintype "passive"))
      (node (ref "C15") (pin "2") (pinfunction "2_2") (pintype "passive"))
      (node (ref "C16") (pin "1") (pinfunction "1_1") (pintype "passive"))
      (node (ref "C17") (pin "1") (pinfunction "1_1") (pintype "passive"))
      (node (ref "C18") (pin "1") (pinfunction "1_1") (pintype "passive"))
      (node (ref "C19") (pin "2") (pinfunction "2_2") (pintype "passive"))
      (node (ref "C2") (pin "2") (pinfunction "2_2") (pintype "passive"))
      (node (ref "C20") (pin "2") (pinfunction "2_2") (pintype "passive"))
      (node (ref "C21") (pin "-") (pinfunction "-_-") (pintype "passive"))
      (node (ref "C22") (pin "1") (pinfunction "1_1") (pintype "passive"))
      (node (ref "C23") (pin "-") (pinfunction "-_-") (pintype "passive"))
      (node (ref "C24") (pin "2") (pinfunction "2_2") (pintype "passive"))
      (node (ref "C25") (pin "-") (pinfunction "-_-") (pintype "passive"))
      (node (ref "C26") (pin "-") (pinfunction "-_-") (pintype "passive"))
      (node (ref "C27") (pin "-") (pinfunction "-_-") (pintype "passive"))
      (node (ref "C3") (pin "2") (pinfunction "2_2") (pintype "passive"))
      (node (ref "C32") (pin "1") (pinfunction "1_1") (pintype "passive"))
      (node (ref "C34") (pin "1") (pinfunction "1_1") (pintype "passive"))
      (node (ref "C4") (pin "2") (pinfunction "2_2") (pintype "passive"))
      (node (ref "C5") (pin "1") (pinfunction "1_1") (pintype "passive"))
      (node (ref "C6") (pin "1") (pinfunction "1_1") (pintype "passive"))
      (node (ref "C7") (pin "2") (pinfunction "2_2") (pintype "passive"))
      (node (ref "C9") (pin "1") (pinfunction "1_1") (pintype "passive"))
      (node (ref "D14") (pin "A") (pinfunction "A_A") (pintype "passive"))
      (node (ref "D15") (pin "1") (pinfunction "A1_1") (pintype "passive"))
      (node (ref "D16") (pin "1") (pinfunction "A1_1") (pintype "passive"))
      (node (ref "DD1") (pin "3") (pinfunction "VSS_3") (pintype "passive"))
      (node (ref "I2C") (pin "3") (pinfunction "3_3") (pintype "passive"))
      (node (ref "IC1") (pin "3") (pinfunction "GND_3") (pintype "power_in"))
      (node (ref "IC10") (pin "3") (pinfunction "GND_3") (pintype "bidirectional"))
      (node (ref "IC2") (pin "2") (pinfunction "GND_2") (pintype "passive"))
      (node (ref "IC2") (pin "2@1") (pinfunction "GND_2@1") (pintype "passive"))
      (node (ref "IC3") (pin "3") (pinfunction "GND_3") (pintype "bidirectional"))
      (node (ref "IC4") (pin "2") (pinfunction "GND_2") (pintype "passive"))
      (node (ref "IC4") (pin "2@1") (pinfunction "GND_2@1") (pintype "passive"))
      (node (ref "IC5") (pin "1") (pinfunction "B_1") (pintype "bidirectional"))
      (node (ref "IC5") (pin "2") (pinfunction "GND_2") (pintype "power_in"))
      (node (ref "IC6") (pin "1") (pinfunction "GND_1") (pintype "power_in"))
      (node (ref "IC7") (pin "2") (pinfunction "GND_2") (pintype "power_in"))
      (node (ref "IC8") (pin "1") (pinfunction "B_1") (pintype "bidirectional"))
      (node (ref "IC8") (pin "2") (pinfunction "GND_2") (pintype "power_in"))
      (node (ref "IC9") (pin "8") (pinfunction "VSS_8") (pintype "power_in"))
      (node (ref "Q1") (pin "2") (pinfunction "S_2") (pintype "passive"))
      (node (ref "Q11") (pin "1") (pinfunction "S_1") (pintype "passive"))
      (node (ref "Q11") (pin "2") (pinfunction "S_2") (pintype "passive"))
      (node (ref "Q11") (pin "3") (pinfunction "S_3") (pintype "passive"))
      (node (ref "Q13") (pin "2") (pinfunction "S_2") (pintype "passive"))
      (node (ref "Q14") (pin "2") (pinfunction "S_2") (pintype "passive"))
      (node (ref "Q2") (pin "2") (pinfunction "S_2") (pintype "passive"))
      (node (ref "Q3") (pin "2") (pinfunction "S_2") (pintype "passive"))
      (node (ref "Q4") (pin "2") (pinfunction "S_2") (pintype "passive"))
      (node (ref "Q5") (pin "2") (pinfunction "S_2") (pintype "passive"))
      (node (ref "Q9") (pin "1") (pinfunction "S_1") (pintype "passive"))
      (node (ref "Q9") (pin "2") (pinfunction "S_2") (pintype "passive"))
      (node (ref "Q9") (pin "3") (pinfunction "S_3") (pintype "passive"))
      (node (ref "R10") (pin "1") (pinfunction "1_1") (pintype "passive"))
      (node (ref "R13") (pin "2") (pinfunction "2_2") (pintype "passive"))
      (node (ref "R15") (pin "1") (pinfunction "1_1") (pintype "passive"))
      (node (ref "R16") (pin "1") (pinfunction "1_1") (pintype "passive"))
      (node (ref "R17") (pin "1") (pinfunction "1_1") (pintype "passive"))
      (node (ref "R27") (pin "1") (pinfunction "1_1") (pintype "passive"))
      (node (ref "R29") (pin "1") (pinfunction "1_1") (pintype "passive"))
      (node (ref "R33") (pin "2") (pinfunction "2_2") (pintype "passive"))
      (node (ref "R35") (pin "1") (pinfunction "1_1") (pintype "passive"))
      (node (ref "R37") (pin "2") (pinfunction "2_2") (pintype "passive"))
      (node (ref "R45") (pin "2") (pinfunction "2_2") (pintype "passive"))
      (node (ref "R59") (pin "2") (pinfunction "2_2") (pintype "passive"))
      (node (ref "R60") (pin "2") (pinfunction "2_2") (pintype "passive"))
      (node (ref "R61") (pin "2") (pinfunction "2_2") (pintype "passive"))
      (node (ref "R62") (pin "2") (pinfunction "2_2") (pintype "passive"))
      (node (ref "R70") (pin "2") (pinfunction "2_2") (pintype "passive"))
      (node (ref "R73") (pin "2") (pinfunction "2_2") (pintype "passive"))
      (node (ref "R76") (pin "2") (pinfunction "2_2") (pintype "passive"))
      (node (ref "R9") (pin "1") (pinfunction "1_1") (pintype "passive"))
      (node (ref "SWD") (pin "4") (pinfunction "4_4") (pintype "passive"))
      (node (ref "U2") (pin "23") (pinfunction "VSS_1_23") (pintype "power_in"))
      (node (ref "U2") (pin "35") (pinfunction "VSS_2_35") (pintype "power_in"))
      (node (ref "U2") (pin "47") (pinfunction "VSS_3_47") (pintype "power_in"))
      (node (ref "U2") (pin "8") (pinfunction "VSSA_8") (pintype "power_in"))
      (node (ref "UART") (pin "3") (pinfunction "3_3") (pintype "passive"))
      (node (ref "UART2") (pin "3") (pinfunction "3_3") (pintype "passive"))
      (node (ref "X0") (pin "14") (pinfunction "GND_14") (pintype "power_in"))
      (node (ref "X0") (pin "20") (pinfunction "GND_20") (pintype "power_in"))
      (node (ref "X0") (pin "25") (pinfunction "GND_25") (pintype "power_in"))
      (node (ref "X0") (pin "6") (pinfunction "GND_6") (pintype "power_in"))
      (node (ref "X0") (pin "9") (pinfunction "GND_9") (pintype "power_in"))
      (node (ref "X15") (pin "2") (pinfunction "KL_2") (pintype "passive"))
      (node (ref "X4") (pin "2") (pinfunction "KL_2") (pintype "passive"))
      (node (ref "X9") (pin "3") (pinfunction "KL_3") (pintype "passive"))
    )
    (net (code "29") (name "Net-(1W-1A-K)") (class "Default")
      (node (ref "1W-1") (pin "1") (pinfunction "K_1") (pintype "passive"))
      (node (ref "L1W1") (pin "A") (pinfunction "A_A") (pintype "passive"))
      (node (ref "Q8") (pin "3") (pinfunction "D_3") (pintype "passive"))
    )
    (net (code "30") (name "Net-(1W-1B-K)") (class "Default")
      (node (ref "1W-1") (pin "2") (pinfunction "K_2") (pintype "passive"))
      (node (ref "D15") (pin "3") (pinfunction "C1A2_3") (pintype "passive"))
      (node (ref "IC5") (pin "4") (pinfunction "X_4") (pintype "bidirectional"))
    )
    (net (code "31") (name "Net-(1W-2A-K)") (class "Default")
      (node (ref "1W-2") (pin "1") (pinfunction "K_1") (pintype "passive"))
      (node (ref "L1W2") (pin "A") (pinfunction "A_A") (pintype "passive"))
      (node (ref "Q10") (pin "3") (pinfunction "D_3") (pintype "passive"))
    )
    (net (code "32") (name "Net-(1W-2B-K)") (class "Default")
      (node (ref "1W-2") (pin "2") (pinfunction "K_2") (pintype "passive"))
      (node (ref "D16") (pin "3") (pinfunction "C1A2_3") (pintype "passive"))
      (node (ref "IC8") (pin "4") (pinfunction "X_4") (pintype "bidirectional"))
    )
    (net (code "33") (name "Net-(A0-P$1)") (class "Default")
      (node (ref "A0") (pin "2") (pinfunction "P$1_2") (pintype "bidirectional"))
      (node (ref "IC9") (pin "3") (pinfunction "A2_3") (pintype "input"))
    )
    (net (code "34") (name "Net-(C21-Pad+)") (class "Default")
      (node (ref "C21") (pin "+") (pinfunction "+_+") (pintype "passive"))
      (node (ref "K1") (pin "2") (pinfunction "2_2") (pintype "passive"))
      (node (ref "R26") (pin "2") (pinfunction "2_2") (pintype "passive"))
    )
    (net (code "35") (name "Net-(C25-Pad+)") (class "Default")
      (node (ref "C25") (pin "+") (pinfunction "+_+") (pintype "passive"))
      (node (ref "K6") (pin "2") (pinfunction "2_2") (pintype "passive"))
      (node (ref "R41") (pin "2") (pinfunction "2_2") (pintype "passive"))
    )
    (net (code "36") (name "Net-(IC1A-1W)") (class "Default")
      (node (ref "IC1") (pin "2") (pinfunction "1W_2") (pintype "open_collector"))
      (node (ref "IC5") (pin "3") (pinfunction "A_3") (pintype "bidirectional"))
      (node (ref "IC8") (pin "3") (pinfunction "A_3") (pintype "bidirectional"))
      (node (ref "Q7") (pin "3") (pinfunction "D_3") (pintype "passive"))
    )
    (net (code "37") (name "Net-(IC1A-PCT)") (class "Default")
      (node (ref "IC1") (pin "6") (pinfunction "PCT_6") (pintype "output"))
      (node (ref "Q7") (pin "1") (pinfunction "G_1") (pintype "passive"))
    )
    (net (code "38") (name "Net-(IC3-OUTF1)") (class "Default")
      (node (ref "IC3") (pin "5") (pinfunction "OUTF1_5") (pintype "bidirectional"))
      (node (ref "IC3") (pin "6") (pinfunction "OUTF2_6") (pintype "bidirectional"))
      (node (ref "X4") (pin "1") (pinfunction "KL_1") (pintype "passive"))
    )
    (net (code "39") (name "Net-(IC3-OUTR1)") (class "Default")
      (node (ref "IC3") (pin "7") (pinfunction "OUTR1_7") (pintype "bidirectional"))
      (node (ref "IC3") (pin "8") (pinfunction "OUTR2_8") (pintype "bidirectional"))
      (node (ref "X4") (pin "3") (pinfunction "KL_3") (pintype "passive"))
    )
    (net (code "40") (name "Net-(IC4-VO)") (class "Default")
      (node (ref "C17") (pin "2") (pinfunction "2_2") (pintype "passive"))
      (node (ref "C18") (pin "2") (pinfunction "2_2") (pintype "passive"))
      (node (ref "C23") (pin "+") (pinfunction "+_+") (pintype "passive"))
      (node (ref "C3") (pin "1") (pinfunction "1_1") (pintype "passive"))
      (node (ref "FB1") (pin "1") (pinfunction "1_1") (pintype "passive"))
      (node (ref "IC4") (pin "1") (pinfunction "VO_1") (pintype "passive"))
      (node (ref "R14") (pin "2") (pinfunction "2_2") (pintype "passive"))
      (node (ref "R8") (pin "2") (pinfunction "2_2") (pintype "passive"))
      (node (ref "SWD") (pin "1") (pinfunction "1_1") (pintype "passive"))
      (node (ref "U2") (pin "24") (pinfunction "VDD_1_24") (pintype "power_in"))
      (node (ref "U2") (pin "36") (pinfunction "VDD_2_36") (pintype "power_in"))
      (node (ref "U2") (pin "48") (pinfunction "VDD_3_48") (pintype "power_in"))
    )
    (net (code "41") (name "Net-(IC6-BST)") (class "Default")
      (node (ref "C8") (pin "1") (pinfunction "1_1") (pintype "passive"))
      (node (ref "IC6") (pin "6") (pinfunction "BST_6") (pintype "input"))
    )
    (net (code "42") (name "Net-(IC6-FB)") (class "Default")
      (node (ref "IC6") (pin "4") (pinfunction "FB_4") (pintype "input"))
      (node (ref "R10") (pin "2") (pinfunction "2_2") (pintype "passive"))
      (node (ref "R11") (pin "2") (pinfunction "2_2") (pintype "passive"))
    )
    (net (code "43") (name "Net-(IC6-SW)") (class "Default")
      (node (ref "C8") (pin "2") (pinfunction "2_2") (pintype "passive"))
      (node (ref "IC6") (pin "2") (pinfunction "SW_2") (pintype "passive"))
      (node (ref "L4.7") (pin "P$1") (pinfunction "1_P$1") (pintype "passive"))
    )
    (net (code "44") (name "Net-(IC9-P0)") (class "Default")
      (node (ref "IC9") (pin "4") (pinfunction "P0_4") (pintype "bidirectional"))
      (node (ref "R47") (pin "2") (pinfunction "2_2") (pintype "passive"))
      (node (ref "R62") (pin "1") (pinfunction "1_1") (pintype "passive"))
    )
    (net (code "45") (name "Net-(IC9-P1)") (class "Default")
      (node (ref "IC9") (pin "5") (pinfunction "P1_5") (pintype "bidirectional"))
      (node (ref "R44") (pin "2") (pinfunction "2_2") (pintype "passive"))
      (node (ref "R61") (pin "1") (pinfunction "1_1") (pintype "passive"))
    )
    (net (code "46") (name "Net-(IC9-P2)") (class "Default")
      (node (ref "IC9") (pin "6") (pinfunction "P2_6") (pintype "bidirectional"))
      (node (ref "R37") (pin "1") (pinfunction "1_1") (pintype "passive"))
      (node (ref "R84") (pin "2") (pinfunction "2_2") (pintype "passive"))
    )
    (net (code "47") (name "Net-(IC9-P3)") (class "Default")
      (node (ref "IC9") (pin "7") (pinfunction "P3_7") (pintype "bidirectional"))
      (node (ref "R73") (pin "1") (pinfunction "1_1") (pintype "passive"))
      (node (ref "R77") (pin "2") (pinfunction "2_2") (pintype "passive"))
    )
    (net (code "48") (name "Net-(IC9-P4)") (class "Default")
      (node (ref "IC9") (pin "9") (pinfunction "P4_9") (pintype "bidirectional"))
      (node (ref "R40") (pin "2") (pinfunction "2_2") (pintype "passive"))
      (node (ref "R59") (pin "1") (pinfunction "1_1") (pintype "passive"))
    )
    (net (code "49") (name "Net-(IC9-P5)") (class "Default")
      (node (ref "IC9") (pin "10") (pinfunction "P5_10") (pintype "bidirectional"))
      (node (ref "R43") (pin "2") (pinfunction "2_2") (pintype "passive"))
      (node (ref "R60") (pin "1") (pinfunction "1_1") (pintype "passive"))
    )
    (net (code "50") (name "Net-(IC10-OUTF1)") (class "Default")
      (node (ref "IC10") (pin "5") (pinfunction "OUTF1_5") (pintype "bidirectional"))
      (node (ref "IC10") (pin "6") (pinfunction "OUTF2_6") (pintype "bidirectional"))
      (node (ref "X15") (pin "1") (pinfunction "KL_1") (pintype "passive"))
    )
    (net (code "51") (name "Net-(IC10-OUTR1)") (class "Default")
      (node (ref "IC10") (pin "7") (pinfunction "OUTR1_7") (pintype "bidirectional"))
      (node (ref "IC10") (pin "8") (pinfunction "OUTR2_8") (pintype "bidirectional"))
      (node (ref "X15") (pin "3") (pinfunction "KL_3") (pintype "passive"))
    )
    (net (code "52") (name "Net-(K2A-PA)") (class "Default")
      (node (ref "K2") (pin "3") (pinfunction "PA_3") (pintype "passive"))
      (node (ref "K2") (pin "6") (pinfunction "PB_6") (pintype "passive"))
      (node (ref "X1") (pin "1") (pinfunction "KL_1") (pintype "passive"))
    )
    (net (code "53") (name "Net-(K2A-SA)") (class "Default")
      (node (ref "K2") (pin "4") (pinfunction "SA_4") (pintype "passive"))
      (node (ref "K2") (pin "5") (pinfunction "SB_5") (pintype "passive"))
      (node (ref "X1") (pin "2") (pinfunction "KL_2") (pintype "passive"))
    )
    (net (code "54") (name "Net-(K2B-2)") (class "Default")
      (node (ref "C27") (pin "+") (pinfunction "+_+") (pintype "passive"))
      (node (ref "K2") (pin "8") (pinfunction "2_8") (pintype "passive"))
      (node (ref "R74") (pin "2") (pinfunction "2_2") (pintype "passive"))
    )
    (net (code "55") (name "Net-(K3A-PA)") (class "Default")
      (node (ref "K3") (pin "3") (pinfunction "PA_3") (pintype "passive"))
      (node (ref "K3") (pin "6") (pinfunction "PB_6") (pintype "passive"))
      (node (ref "X2") (pin "1") (pinfunction "KL_1") (pintype "passive"))
    )
    (net (code "56") (name "Net-(K3A-SA)") (class "Default")
      (node (ref "K3") (pin "4") (pinfunction "SA_4") (pintype "passive"))
      (node (ref "K3") (pin "5") (pinfunction "SB_5") (pintype "passive"))
      (node (ref "X2") (pin "2") (pinfunction "KL_2") (pintype "passive"))
    )
    (net (code "57") (name "Net-(K3B-2)") (class "Default")
      (node (ref "C26") (pin "+") (pinfunction "+_+") (pintype "passive"))
      (node (ref "K3") (pin "8") (pinfunction "2_8") (pintype "passive"))
      (node (ref "R82") (pin "2") (pinfunction "2_2") (pintype "passive"))
    )
    (net (code "58") (name "Net-(L1W1-PadC)") (class "Default")
      (node (ref "L1W1") (pin "C") (pinfunction "C_C") (pintype "passive"))
      (node (ref "R76") (pin "1") (pinfunction "1_1") (pintype "passive"))
    )
    (net (code "59") (name "Net-(L1W2-PadC)") (class "Default")
      (node (ref "L1W2") (pin "C") (pinfunction "C_C") (pintype "passive"))
      (node (ref "R45") (pin "1") (pinfunction "1_1") (pintype "passive"))
    )
    (net (code "60") (name "Net-(L4.7-2)") (class "Default")
      (node (ref "C14") (pin "+") (pinfunction "+_+") (pintype "passive"))
      (node (ref "C22") (pin "2") (pinfunction "2_2") (pintype "passive"))
      (node (ref "C9") (pin "2") (pinfunction "2_2") (pintype "passive"))
      (node (ref "L4.7") (pin "P$2") (pinfunction "2_P$2") (pintype "passive"))
      (node (ref "R11") (pin "1") (pinfunction "1_1") (pintype "passive"))
      (node (ref "R5") (pin "2") (pinfunction "2_2") (pintype "passive"))
      (node (ref "X0") (pin "2") (pinfunction "5V_2") (pintype "power_in"))
      (node (ref "X0") (pin "4") (pinfunction "5V_4") (pintype "power_in"))
    )
    (net (code "61") (name "Net-(LED1-PadC)") (class "Default")
      (node (ref "LED1") (pin "C") (pinfunction "C_C") (pintype "passive"))
      (node (ref "R22") (pin "1") (pinfunction "1_1") (pintype "passive"))
    )
    (net (code "62") (name "Net-(LED2-PadC)") (class "Default")
      (node (ref "LED2") (pin "C") (pinfunction "C_C") (pintype "passive"))
      (node (ref "R23") (pin "1") (pinfunction "1_1") (pintype "passive"))
    )
    (net (code "63") (name "Net-(LED3-PadC)") (class "Default")
      (node (ref "LED3") (pin "C") (pinfunction "C_C") (pintype "passive"))
      (node (ref "R75") (pin "1") (pinfunction "1_1") (pintype "passive"))
    )
    (net (code "64") (name "Net-(LED4-PadC)") (class "Default")
      (node (ref "LED4") (pin "C") (pinfunction "C_C") (pintype "passive"))
      (node (ref "R83") (pin "1") (pinfunction "1_1") (pintype "passive"))
    )
    (net (code "65") (name "Net-(LED7-PadC)") (class "Default")
      (node (ref "LED7") (pin "C") (pinfunction "C_C") (pintype "passive"))
      (node (ref "R36") (pin "1") (pinfunction "1_1") (pintype "passive"))
    )
    (net (code "66") (name "Net-(LED8-PadC)") (class "Default")
      (node (ref "LED8") (pin "C") (pinfunction "C_C") (pintype "passive"))
      (node (ref "R42") (pin "1") (pinfunction "1_1") (pintype "passive"))
    )
    (net (code "67") (name "Net-(LED9-PadC)") (class "Default")
      (node (ref "LED9") (pin "C") (pinfunction "C_C") (pintype "passive"))
      (node (ref "R25") (pin "1") (pinfunction "1_1") (pintype "passive"))
    )
    (net (code "68") (name "Net-(LED10-PadC)") (class "Default")
      (node (ref "LED10") (pin "C") (pinfunction "C_C") (pintype "passive"))
      (node (ref "R64") (pin "1") (pinfunction "1_1") (pintype "passive"))
    )
    (net (code "69") (name "Net-(Q1-D)") (class "Default")
      (node (ref "D3") (pin "A") (pinfunction "A_A") (pintype "passive"))
      (node (ref "Q1") (pin "3") (pinfunction "D_3") (pintype "passive"))
      (node (ref "Q9") (pin "5") (pinfunction "D_5") (pintype "passive"))
      (node (ref "Q9") (pin "6") (pinfunction "D_6") (pintype "passive"))
      (node (ref "Q9") (pin "7") (pinfunction "D_7") (pintype "passive"))
      (node (ref "Q9") (pin "8") (pinfunction "D_8") (pintype "passive"))
      (node (ref "R25") (pin "2") (pinfunction "2_2") (pintype "passive"))
      (node (ref "X10") (pin "2") (pinfunction "KL_2") (pintype "passive"))
    )
    (net (code "70") (name "Net-(Q1-G)") (class "Default")
      (node (ref "Q1") (pin "1") (pinfunction "G_1") (pintype "passive"))
      (node (ref "Q9") (pin "4") (pinfunction "G_4") (pintype "passive"))
      (node (ref "R44") (pin "1") (pinfunction "1_1") (pintype "passive"))
    )
    (net (code "71") (name "Net-(Q2-D)") (class "Default")
      (node (ref "Q2") (pin "3") (pinfunction "D_3") (pintype "passive"))
      (node (ref "R28") (pin "1") (pinfunction "1_1") (pintype "passive"))
    )
    (net (code "72") (name "Net-(Q2-G)") (class "Default")
      (node (ref "Q2") (pin "1") (pinfunction "G_1") (pintype "passive"))
      (node (ref "R71") (pin "2") (pinfunction "2_2") (pintype "passive"))
    )
    (net (code "73") (name "Net-(Q3-D)") (class "Default")
      (node (ref "D1") (pin "A") (pinfunction "A_A") (pintype "passive"))
      (node (ref "K1") (pin "1") (pinfunction "1_1") (pintype "passive"))
      (node (ref "Q3") (pin "3") (pinfunction "D_3") (pintype "passive"))
      (node (ref "R36") (pin "2") (pinfunction "2_2") (pintype "passive"))
    )
    (net (code "74") (name "Net-(Q3-G)") (class "Default")
      (node (ref "Q3") (pin "1") (pinfunction "G_1") (pintype "passive"))
      (node (ref "R40") (pin "1") (pinfunction "1_1") (pintype "passive"))
    )
    (net (code "75") (name "Net-(Q4-D)") (class "Default")
      (node (ref "D2") (pin "A") (pinfunction "A_A") (pintype "passive"))
      (node (ref "K6") (pin "1") (pinfunction "1_1") (pintype "passive"))
      (node (ref "Q4") (pin "3") (pinfunction "D_3") (pintype "passive"))
      (node (ref "R42") (pin "2") (pinfunction "2_2") (pintype "passive"))
    )
    (net (code "76") (name "Net-(Q4-G)") (class "Default")
      (node (ref "Q4") (pin "1") (pinfunction "G_1") (pintype "passive"))
      (node (ref "R43") (pin "1") (pinfunction "1_1") (pintype "passive"))
    )
    (net (code "77") (name "Net-(Q5-D)") (class "Default")
      (node (ref "D4") (pin "A") (pinfunction "A_A") (pintype "passive"))
      (node (ref "Q11") (pin "5") (pinfunction "D_5") (pintype "passive"))
      (node (ref "Q11") (pin "6") (pinfunction "D_6") (pintype "passive"))
      (node (ref "Q11") (pin "7") (pinfunction "D_7") (pintype "passive"))
      (node (ref "Q11") (pin "8") (pinfunction "D_8") (pintype "passive"))
      (node (ref "Q5") (pin "3") (pinfunction "D_3") (pintype "passive"))
      (node (ref "R64") (pin "2") (pinfunction "2_2") (pintype "passive"))
      (node (ref "X11") (pin "2") (pinfunction "KL_2") (pintype "passive"))
    )
    (net (code "78") (name "Net-(Q8-G)") (class "Default")
      (node (ref "Q8") (pin "1") (pinfunction "G_1") (pintype "passive"))
      (node (ref "R31") (pin "2") (pinfunction "2_2") (pintype "passive"))
    )
    (net (code "79") (name "Net-(Q10-G)") (class "Default")
      (node (ref "Q10") (pin "1") (pinfunction "G_1") (pintype "passive"))
      (node (ref "R32") (pin "2") (pinfunction "2_2") (pintype "passive"))
    )
    (net (code "80") (name "Net-(Q11-G)") (class "Default")
      (node (ref "Q11") (pin "4") (pinfunction "G_4") (pintype "passive"))
      (node (ref "Q5") (pin "1") (pinfunction "G_1") (pintype "passive"))
      (node (ref "R47") (pin "1") (pinfunction "1_1") (pintype "passive"))
    )
    (net (code "81") (name "Net-(Q13-D)") (class "Default")
      (node (ref "D19") (pin "A") (pinfunction "A_A") (pintype "passive"))
      (node (ref "K2") (pin "1") (pinfunction "1_1") (pintype "passive"))
      (node (ref "Q13") (pin "3") (pinfunction "D_3") (pintype "passive"))
      (node (ref "R75") (pin "2") (pinfunction "2_2") (pintype "passive"))
    )
    (net (code "82") (name "Net-(Q13-G)") (class "Default")
      (node (ref "Q13") (pin "1") (pinfunction "G_1") (pintype "passive"))
      (node (ref "R77") (pin "1") (pinfunction "1_1") (pintype "passive"))
    )
    (net (code "83") (name "Net-(Q14-D)") (class "Default")
      (node (ref "D21") (pin "A") (pinfunction "A_A") (pintype "passive"))
      (node (ref "K3") (pin "1") (pinfunction "1_1") (pintype "passive"))
      (node (ref "Q14") (pin "3") (pinfunction "D_3") (pintype "passive"))
      (node (ref "R83") (pin "2") (pinfunction "2_2") (pintype "passive"))
    )
    (net (code "84") (name "Net-(Q14-G)") (class "Default")
      (node (ref "Q14") (pin "1") (pinfunction "G_1") (pintype "passive"))
      (node (ref "R84") (pin "1") (pinfunction "1_1") (pintype "passive"))
    )
    (net (code "85") (name "Net-(U2-VBAT)") (class "Default")
      (node (ref "C2") (pin "1") (pinfunction "1_1") (pintype "passive"))
      (node (ref "FB1") (pin "2") (pinfunction "2_2") (pintype "passive"))
      (node (ref "U2") (pin "1") (pinfunction "VBAT_1") (pintype "power_in"))
      (node (ref "U2") (pin "9") (pinfunction "VDDA_9") (pintype "power_in"))
    )
    (net (code "86") (name "Net-(X0-PWM1{slash}PA06)") (class "Default")
      (node (ref "R70") (pin "1") (pinfunction "1_1") (pintype "passive"))
      (node (ref "R71") (pin "1") (pinfunction "1_1") (pintype "passive"))
      (node (ref "X0") (pin "7") (pinfunction "PWM1/PA06_7") (pintype "bidirectional"))
    )
    (net (code "87") (name "Net-(X0-UART1_RX{slash}PG07)") (class "Default")
      (node (ref "R1") (pin "2") (pinfunction "2_2") (pintype "passive"))
      (node (ref "R3") (pin "2") (pinfunction "2_2") (pintype "passive"))
      (node (ref "UART") (pin "2") (pinfunction "2_2") (pintype "passive"))
      (node (ref "X0") (pin "10") (pinfunction "UART1_RX/PG07_10") (pintype "bidirectional"))
    )
    (net (code "88") (name "Net-(X0-UART1_TX{slash}PG06)") (class "Default")
      (node (ref "R2") (pin "2") (pinfunction "2_2") (pintype "passive"))
      (node (ref "R4") (pin "2") (pinfunction "2_2") (pintype "passive"))
      (node (ref "UART") (pin "1") (pinfunction "1_1") (pintype "passive"))
      (node (ref "X0") (pin "8") (pinfunction "UART1_TX/PG06_8") (pintype "bidirectional"))
    )
    (net (code "89") (name "Net-(X0-UART2_RX{slash}PA01)") (class "Default")
      (node (ref "UART2") (pin "2") (pinfunction "2_2") (pintype "passive"))
      (node (ref "X0") (pin "11") (pinfunction "UART2_RX/PA01_11") (pintype "bidirectional"))
    )
    (net (code "90") (name "Net-(X0-UART2_TX{slash}PA00)") (class "Default")
      (node (ref "UART2") (pin "1") (pinfunction "1_1") (pintype "passive"))
      (node (ref "X0") (pin "13") (pinfunction "UART2_TX/PA00_13") (pintype "bidirectional"))
    )
    (net (code "91") (name "Net-(X6A-KL)") (class "Default")
      (node (ref "K1") (pin "O") (pinfunction "O_O") (pintype "passive"))
      (node (ref "X6") (pin "1") (pinfunction "KL_1") (pintype "passive"))
    )
    (net (code "92") (name "Net-(X6B-KL)") (class "Default")
      (node (ref "K1") (pin "P") (pinfunction "P_P") (pintype "passive"))
      (node (ref "X6") (pin "2") (pinfunction "KL_2") (pintype "passive"))
    )
    (net (code "93") (name "Net-(X6C-KL)") (class "Default")
      (node (ref "K1") (pin "S") (pinfunction "S_S") (pintype "passive"))
      (node (ref "X6") (pin "3") (pinfunction "KL_3") (pintype "passive"))
    )
    (net (code "94") (name "Net-(X8A-KL)") (class "Default")
      (node (ref "K6") (pin "O") (pinfunction "O_O") (pintype "passive"))
      (node (ref "X8") (pin "1") (pinfunction "KL_1") (pintype "passive"))
    )
    (net (code "95") (name "Net-(X8B-KL)") (class "Default")
      (node (ref "K6") (pin "P") (pinfunction "P_P") (pintype "passive"))
      (node (ref "X8") (pin "2") (pinfunction "KL_2") (pintype "passive"))
    )
    (net (code "96") (name "Net-(X8C-KL)") (class "Default")
      (node (ref "K6") (pin "S") (pinfunction "S_S") (pintype "passive"))
      (node (ref "X8") (pin "3") (pinfunction "KL_3") (pintype "passive"))
    )
    (net (code "97") (name "Net-(X9A-KL)") (class "Default")
      (node (ref "D10") (pin "A") (pinfunction "A_A") (pintype "passive"))
      (node (ref "R30") (pin "1") (pinfunction "1_1") (pintype "passive"))
      (node (ref "X9") (pin "1") (pinfunction "KL_1") (pintype "passive"))
    )
    (net (code "98") (name "VDD") (class "Default")
      (node (ref "C20") (pin "1") (pinfunction "1_1") (pintype "passive"))
      (node (ref "C24") (pin "1") (pinfunction "1_1") (pintype "passive"))
      (node (ref "C4") (pin "1") (pinfunction "1_1") (pintype "passive"))
      (node (ref "C7") (pin "1") (pinfunction "1_1") (pintype "passive"))
      (node (ref "D14") (pin "C") (pinfunction "C_C") (pintype "passive"))
      (node (ref "D15") (pin "2") (pinfunction "C2_2") (pintype "passive"))
      (node (ref "D16") (pin "2") (pinfunction "C2_2") (pintype "passive"))
      (node (ref "DD1") (pin "2") (pinfunction "VDD_2") (pintype "input"))
      (node (ref "IC2") (pin "3") (pinfunction "VI_3") (pintype "input"))
      (node (ref "LED1") (pin "A") (pinfunction "A_A") (pintype "passive"))
      (node (ref "LED2") (pin "A") (pinfunction "A_A") (pintype "passive"))
      (node (ref "Q10") (pin "2") (pinfunction "S_2") (pintype "passive"))
      (node (ref "Q7") (pin "2") (pinfunction "S_2") (pintype "passive"))
      (node (ref "Q8") (pin "2") (pinfunction "S_2") (pintype "passive"))
      (node (ref "R27") (pin "2") (pinfunction "2_2") (pintype "passive"))
      (node (ref "R38") (pin "2") (pinfunction "2_2") (pintype "passive"))
      (node (ref "R39") (pin "2") (pinfunction "2_2") (pintype "passive"))
    )
    (net (code "99") (name "unconnected-(IC7-NC-Pad3)") (class "Default")
      (node (ref "IC7") (pin "3") (pinfunction "NC_3") (pintype "no_connect"))
    )
    (net (code "100") (name "unconnected-(IC9-~{INT}-Pad13)") (class "Default")
      (node (ref "IC9") (pin "13") (pinfunction "~{INT}_13") (pintype "output"))
    )
    (net (code "101") (name "unconnected-(K2A-OA-Pad2)") (class "Default")
      (node (ref "K2") (pin "2") (pinfunction "OA_2") (pintype "passive"))
    )
    (net (code "102") (name "unconnected-(K2A-OB-Pad7)") (class "Default")
      (node (ref "K2") (pin "7") (pinfunction "OB_7") (pintype "passive"))
    )
    (net (code "103") (name "unconnected-(K3A-OA-Pad2)") (class "Default")
      (node (ref "K3") (pin "2") (pinfunction "OA_2") (pintype "passive"))
    )
    (net (code "104") (name "unconnected-(K3A-OB-Pad7)") (class "Default")
      (node (ref "K3") (pin "7") (pinfunction "OB_7") (pintype "passive"))
    )
    (net (code "105") (name "unconnected-(U2-BOOT0-Pad44)") (class "Default")
      (node (ref "U2") (pin "44") (pinfunction "BOOT0_44") (pintype "input"))
    )
    (net (code "106") (name "unconnected-(U2-PA4-Pad14)") (class "Default")
      (node (ref "U2") (pin "14") (pinfunction "PA4_14") (pintype "bidirectional"))
    )
    (net (code "107") (name "unconnected-(U2-PA5-Pad15)") (class "Default")
      (node (ref "U2") (pin "15") (pinfunction "PA5_15") (pintype "bidirectional"))
    )
    (net (code "108") (name "unconnected-(U2-PA6-Pad16)") (class "Default")
      (node (ref "U2") (pin "16") (pinfunction "PA6_16") (pintype "bidirectional"))
    )
    (net (code "109") (name "unconnected-(U2-PA7-Pad17)") (class "Default")
      (node (ref "U2") (pin "17") (pinfunction "PA7_17") (pintype "bidirectional"))
    )
    (net (code "110") (name "unconnected-(U2-PA8-Pad29)") (class "Default")
      (node (ref "U2") (pin "29") (pinfunction "PA8_29") (pintype "bidirectional"))
    )
    (net (code "111") (name "unconnected-(U2-PA15-Pad38)") (class "Default")
      (node (ref "U2") (pin "38") (pinfunction "PA15_38") (pintype "bidirectional"))
    )
    (net (code "112") (name "unconnected-(U2-PB0-Pad18)") (class "Default")
      (node (ref "U2") (pin "18") (pinfunction "PB0_18") (pintype "bidirectional"))
    )
    (net (code "113") (name "unconnected-(U2-PB1-Pad19)") (class "Default")
      (node (ref "U2") (pin "19") (pinfunction "PB1_19") (pintype "bidirectional"))
    )
    (net (code "114") (name "unconnected-(U2-PB2-Pad20)") (class "Default")
      (node (ref "U2") (pin "20") (pinfunction "PB2_20") (pintype "bidirectional"))
    )
    (net (code "115") (name "unconnected-(U2-PB5-Pad41)") (class "Default")
      (node (ref "U2") (pin "41") (pinfunction "PB5_41") (pintype "bidirectional"))
    )
    (net (code "116") (name "unconnected-(U2-PB10-Pad21)") (class "Default")
      (node (ref "U2") (pin "21") (pinfunction "PB10_21") (pintype "bidirectional"))
    )
    (net (code "117") (name "unconnected-(U2-PB11-Pad22)") (class "Default")
      (node (ref "U2") (pin "22") (pinfunction "PB11_22") (pintype "bidirectional"))
    )
    (net (code "118") (name "unconnected-(U2-PB12-Pad25)") (class "Default")
      (node (ref "U2") (pin "25") (pinfunction "PB12_25") (pintype "bidirectional"))
    )
    (net (code "119") (name "unconnected-(U2-PB13-Pad26)") (class "Default")
      (node (ref "U2") (pin "26") (pinfunction "PB13_26") (pintype "bidirectional"))
    )
    (net (code "120") (name "unconnected-(U2-PC14-OSC32_IN-Pad3)") (class "Default")
      (node (ref "U2") (pin "3") (pinfunction "PC14-OSC32_IN_3") (pintype "bidirectional"))
    )
    (net (code "121") (name "unconnected-(U2-PC15-OSC32_OUT-Pad4)") (class "Default")
      (node (ref "U2") (pin "4") (pinfunction "PC15-OSC32_OUT_4") (pintype "bidirectional"))
    )
    (net (code "122") (name "unconnected-(U2-PD0-OSC_IN-Pad5)") (class "Default")
      (node (ref "U2") (pin "5") (pinfunction "PD0-OSC_IN_5") (pintype "input"))
    )
    (net (code "123") (name "unconnected-(U2-PD1-OSC_OUT-Pad6)") (class "Default")
      (node (ref "U2") (pin "6") (pinfunction "PD1-OSC_OUT_6") (pintype "output"))
    )
    (net (code "124") (name "unconnected-(X0-PA13{slash}SPI1_CS-Pad24)") (class "Default")
      (node (ref "X0") (pin "24") (pinfunction "PA13/SPI1_CS_24") (pintype "bidirectional"))
    )
    (net (code "125") (name "unconnected-(X0-PA14{slash}SPI1_CLK-Pad23)") (class "Default")
      (node (ref "X0") (pin "23") (pinfunction "PA14/SPI1_CLK_23") (pintype "bidirectional"))
    )
    (net (code "126") (name "unconnected-(X0-PA15{slash}SPI1_MOSI-Pad19)") (class "Default")
      (node (ref "X0") (pin "19") (pinfunction "PA15/SPI1_MOSI_19") (pintype "bidirectional"))
    )
    (net (code "127") (name "unconnected-(X0-PA16{slash}SPI1_MISO-Pad21)") (class "Default")
      (node (ref "X0") (pin "21") (pinfunction "PA16/SPI1_MISO_21") (pintype "bidirectional"))
    )
    (net (code "128") (name "unconnected-(X0-PA18{slash}TWI1_SCL-Pad18)") (class "Default")
      (node (ref "X0") (pin "18") (pinfunction "PA18/TWI1_SCL_18") (pintype "bidirectional"))
    )
    (net (code "129") (name "unconnected-(X0-PA19{slash}TWI1_SDA-Pad16)") (class "Default")
      (node (ref "X0") (pin "16") (pinfunction "PA19/TWI1_SDA_16") (pintype "bidirectional"))
    )
    (net (code "130") (name "unconnected-(X0-SIM_DET{slash}PA_EINT10{slash}PA10-Pad26)") (class "Default")
      (node (ref "X0") (pin "26") (pinfunction "SIM_DET/PA_EINT10/PA10_26") (pintype "bidirectional"))
    )
    (net (code "131") (name "unconnected-(X0-UART2_CTS{slash}PA03-Pad15)") (class "Default")
      (node (ref "X0") (pin "15") (pinfunction "UART2_CTS/PA03_15") (pintype "bidirectional"))
    )
    (net (code "132") (name "unconnected-(X0-UART2_RTS{slash}PA02-Pad22)") (class "Default")
      (node (ref "X0") (pin "22") (pinfunction "UART2_RTS/PA02_22") (pintype "bidirectional"))
    )
  )
)
